# Sht3-Regulators.net
KiCad netlist of a schematic drawn in Altium Designer
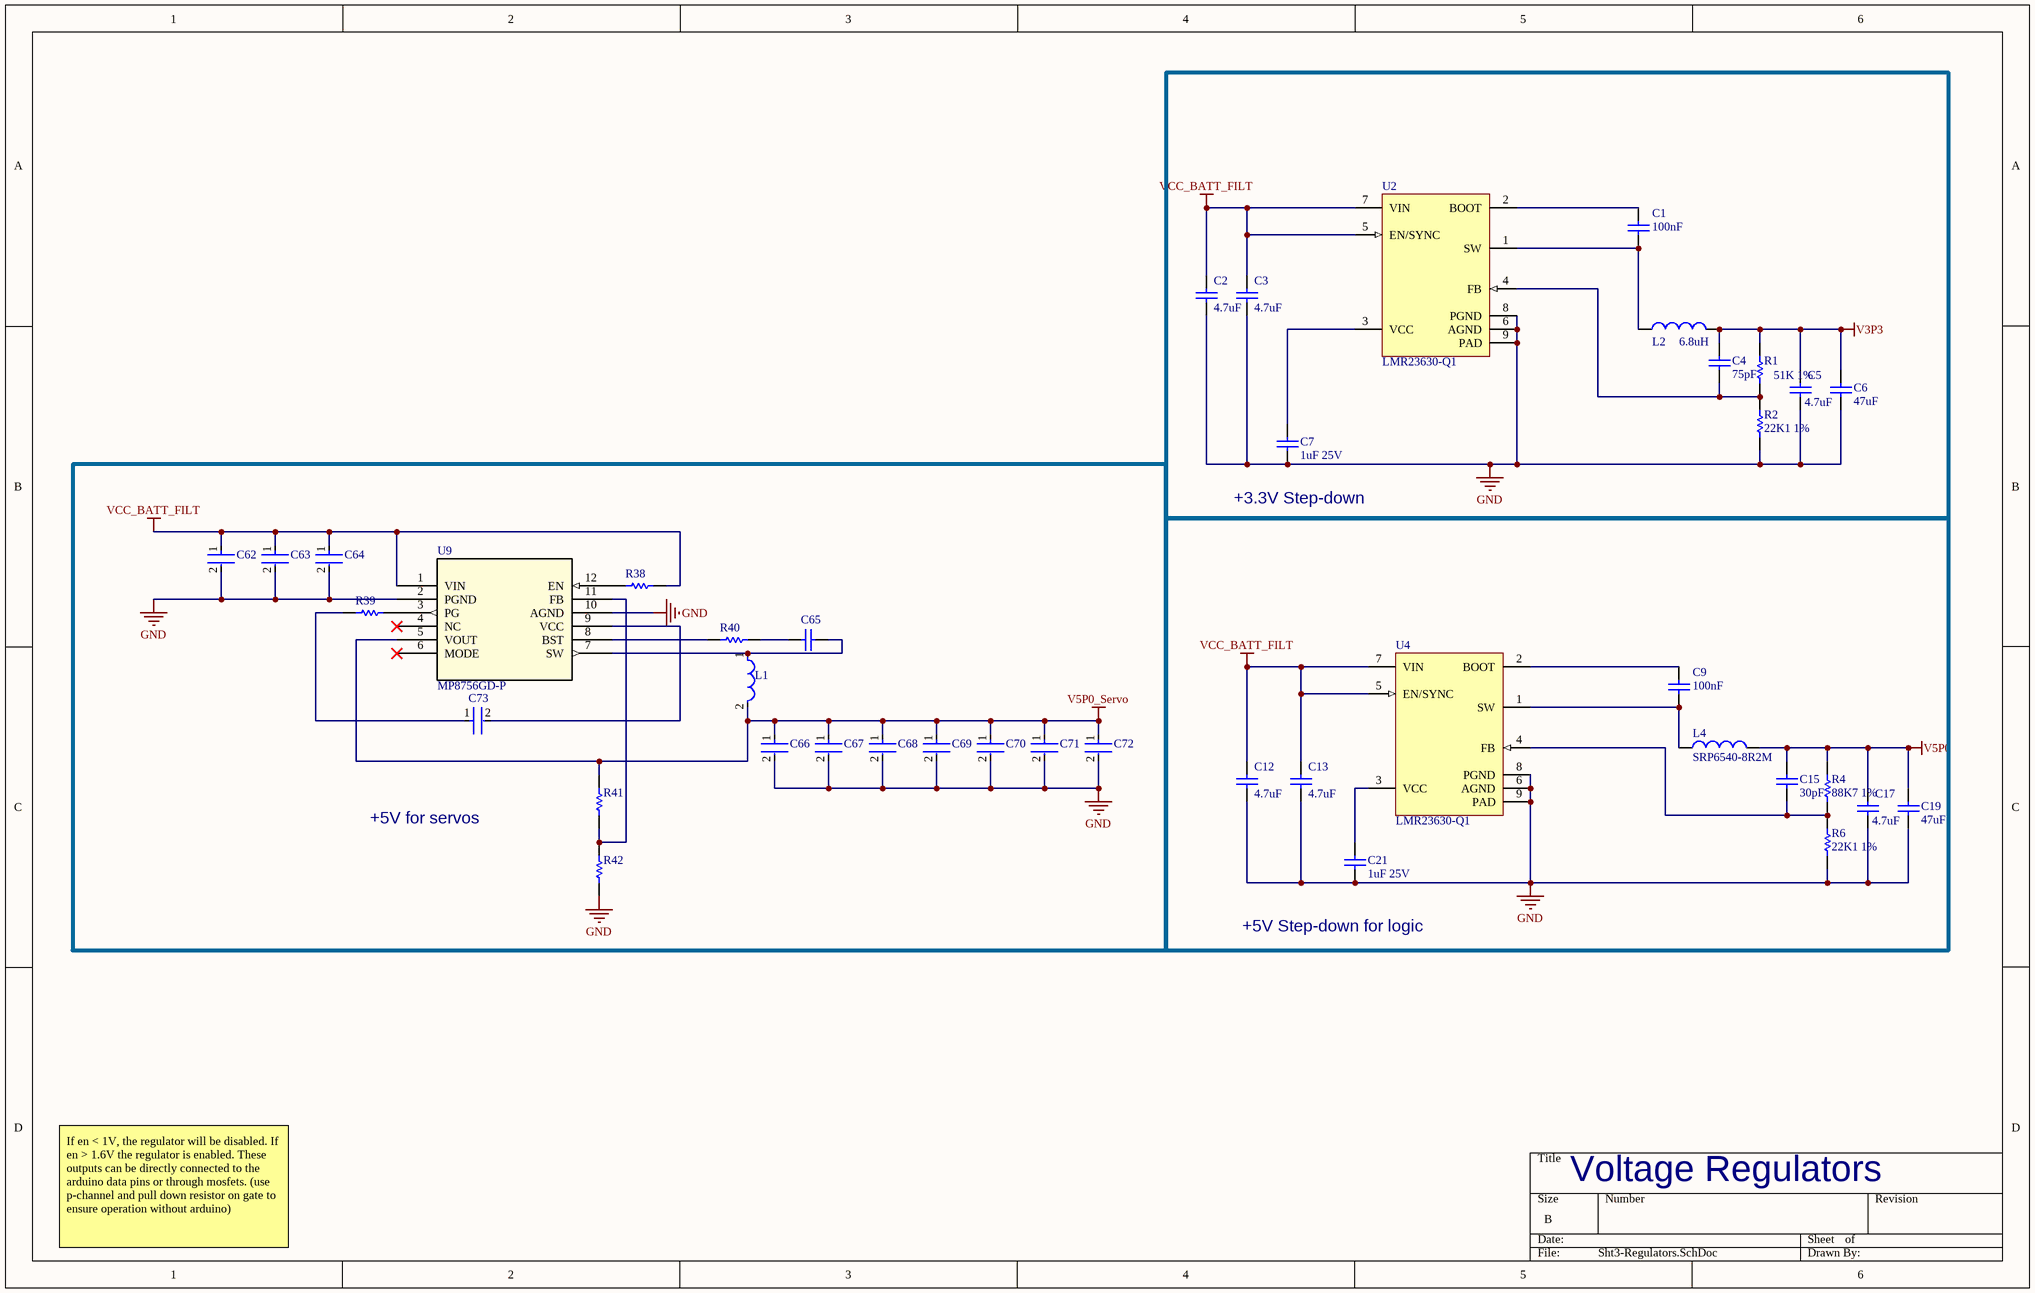
[diagram p0: Sht3-Regulators.SchDoc]

(export (version "E")
  (design (tool "Eeschema 10.0.6"))
  (components
    (comp (ref "C1")
      (value "100nF")
      (footprint "CAPC0603(1608)100_L")
      (description "CAP 100nF 100V ±10% 0603 (1608 Metric) Thickness 1mm SMD")
      (fields (field (name "TOLERANCE") "Â±10%"))
      (libsource (lib "Altium Content Vault") (part "CAP"))
    )
    (comp (ref "C2")
      (value "4.7uF")
      (footprint "CAPC1206(3216)190_L")
      (description "CAP 4.7uF 35V ±10% 1206 (3216 Metric) Thickness 1.9mm SMD")
      (fields (field (name "TOLERANCE") "Â±10%"))
      (libsource (lib "Altium Content Vault") (part "CAP"))
    )
    (comp (ref "C3")
      (value "4.7uF")
      (footprint "CAPC1206(3216)190_L")
      (description "CAP 4.7uF 35V ±10% 1206 (3216 Metric) Thickness 1.9mm SMD")
      (fields (field (name "TOLERANCE") "Â±10%"))
      (libsource (lib "Altium Content Vault") (part "CAP"))
    )
    (comp (ref "C4")
      (value "75pF")
      (footprint "CAPC0603(1608)100_L")
      (description "CAP 75pF 25V ±1% 0603 (1608 Metric) Thickness 1mm SMD")
      (fields (field (name "TOLERANCE") "Â±1%"))
      (libsource (lib "Altium Content Vault") (part "CAP"))
    )
    (comp (ref "C5")
      (value "4.7uF")
      (footprint "CAPC1206(3216)190_L")
      (description "CAP 4.7uF 35V ±10% 1206 (3216 Metric) Thickness 1.9mm SMD")
      (fields (field (name "TOLERANCE") "Â±10%"))
      (libsource (lib "Altium Content Vault") (part "CAP"))
    )
    (comp (ref "C6")
      (value "47uF")
      (footprint "CAPC1206(3216)190_L")
      (description "CAP 47uF 16V ±20% 1206 (3216 Metric) Thickness 1.9mm SMD")
      (fields (field (name "TOLERANCE") "Â±20%"))
      (libsource (lib "Altium Content Vault") (part "CAP"))
    )
    (comp (ref "C7")
      (value "1uF 25V")
      (footprint "CAPC0603(1608)100_L")
      (description "CAP 1uF 25V ±10% 0603 (1608 Metric) Thickness 1mm SMD")
      (fields (field (name "TOLERANCE") "Â±10%"))
      (libsource (lib "Altium Content Vault") (part "CAP"))
    )
    (comp (ref "C9")
      (value "100nF")
      (footprint "CAPC0603(1608)100_L")
      (description "CAP 100nF 100V ±10% 0603 (1608 Metric) Thickness 1mm SMD")
      (fields (field (name "TOLERANCE") "Â±10%"))
      (libsource (lib "Altium Content Vault") (part "CAP"))
    )
    (comp (ref "C12")
      (value "4.7uF")
      (footprint "CAPC1206(3216)190_L")
      (description "CAP 4.7uF 35V ±10% 1206 (3216 Metric) Thickness 1.9mm SMD")
      (fields (field (name "TOLERANCE") "Â±10%"))
      (libsource (lib "Altium Content Vault") (part "CAP"))
    )
    (comp (ref "C13")
      (value "4.7uF")
      (footprint "CAPC1206(3216)190_L")
      (description "CAP 4.7uF 35V ±10% 1206 (3216 Metric) Thickness 1.9mm SMD")
      (fields (field (name "TOLERANCE") "Â±10%"))
      (libsource (lib "Altium Content Vault") (part "CAP"))
    )
    (comp (ref "C15")
      (value "30pF")
      (footprint "CAPC0603(1608)100_L")
      (description "CAP 30pF 50V ±10% 0603 (1608 Metric) Thickness 1mm SMD")
      (fields (field (name "TOLERANCE") "Â±10%"))
      (libsource (lib "Altium Content Vault") (part "CAP"))
    )
    (comp (ref "C17")
      (value "4.7uF")
      (footprint "CAPC1206(3216)190_L")
      (description "CAP 4.7uF 35V ±10% 1206 (3216 Metric) Thickness 1.9mm SMD")
      (fields (field (name "TOLERANCE") "Â±10%"))
      (libsource (lib "Altium Content Vault") (part "CAP"))
    )
    (comp (ref "C19")
      (value "47uF")
      (footprint "CAPC1206(3216)190_L")
      (description "CAP 47uF 16V ±20% 1206 (3216 Metric) Thickness 1.9mm SMD")
      (fields (field (name "TOLERANCE") "Â±20%"))
      (libsource (lib "Altium Content Vault") (part "CAP"))
    )
    (comp (ref "C21")
      (value "1uF 25V")
      (footprint "CAPC0603(1608)100_L")
      (description "CAP 1uF 25V ±10% 0603 (1608 Metric) Thickness 1mm SMD")
      (fields (field (name "TOLERANCE") "Â±10%"))
      (libsource (lib "Altium Content Vault") (part "CAP"))
    )
    (comp (ref "C62")
      (value "CC0603KRX7R9BB104")
      (footprint "FP-CC0603-DA-MFG")
      (description "CAP CER 0.1UF 50V X7R 0603")
      (fields (field (name "MANUFACTURER") "YAGEO") (field (name "VOLTAGE") "50 V"))
      (libsource (lib "Altium Content Vault") (part "11868f565c42a9108669ba33697ecf6"))
    )
    (comp (ref "C63")
      (value "CL10A226MPCNUBE")
      (footprint "FP-CL10-IPC_B")
      (description "Cap Ceramic 22uF 10V X5R ±20% Pad SMD 0603 +85°C T/R")
      (fields (field (name "TOLERANCE") "20%"))
      (libsource (lib "Altium Content Vault") (part "b4654b650e69147ec39a6b967a45e02"))
    )
    (comp (ref "C64")
      (value "CL10A226MPCNUBE")
      (footprint "FP-CL10-IPC_B")
      (description "Cap Ceramic 22uF 10V X5R ±20% Pad SMD 0603 +85°C T/R")
      (fields (field (name "TOLERANCE") "20%"))
      (libsource (lib "Altium Content Vault") (part "b4654b650e69147ec39a6b967a45e02"))
    )
    (comp (ref "C65")
      (value "C0603C224K8NACTU")
      (footprint "CAPC1608X87X35NL15T15")
      (description "220nF 0603")
      (fields (field (name "MANUFACTURER") "Kemet"))
      (libsource (lib "Altium Content Vault") (part "CAP"))
    )
    (comp (ref "C66")
      (value "CL10A226MPCNUBE")
      (footprint "FP-CL10-IPC_B")
      (description "Cap Ceramic 22uF 10V X5R ±20% Pad SMD 0603 +85°C T/R")
      (fields (field (name "TOLERANCE") "20%"))
      (libsource (lib "Altium Content Vault") (part "b4654b650e69147ec39a6b967a45e02"))
    )
    (comp (ref "C67")
      (value "CL10A226MPCNUBE")
      (footprint "FP-CL10-IPC_B")
      (description "Cap Ceramic 22uF 10V X5R ±20% Pad SMD 0603 +85°C T/R")
      (fields (field (name "TOLERANCE") "20%"))
      (libsource (lib "Altium Content Vault") (part "b4654b650e69147ec39a6b967a45e02"))
    )
    (comp (ref "C68")
      (value "CL10A226MPCNUBE")
      (footprint "FP-CL10-IPC_B")
      (description "Cap Ceramic 22uF 10V X5R ±20% Pad SMD 0603 +85°C T/R")
      (fields (field (name "TOLERANCE") "20%"))
      (libsource (lib "Altium Content Vault") (part "b4654b650e69147ec39a6b967a45e02"))
    )
    (comp (ref "C69")
      (value "CL10A226MPCNUBE")
      (footprint "FP-CL10-IPC_B")
      (description "Cap Ceramic 22uF 10V X5R ±20% Pad SMD 0603 +85°C T/R")
      (fields (field (name "TOLERANCE") "20%"))
      (libsource (lib "Altium Content Vault") (part "b4654b650e69147ec39a6b967a45e02"))
    )
    (comp (ref "C70")
      (value "CC0603KRX7R9BB104")
      (footprint "FP-CC0603-DA-MFG")
      (description "CAP CER 0.1UF 50V X7R 0603")
      (fields (field (name "MANUFACTURER") "YAGEO") (field (name "VOLTAGE") "50 V"))
      (libsource (lib "Altium Content Vault") (part "11868f565c42a9108669ba33697ecf6"))
    )
    (comp (ref "C71")
      (value "CC0603KRX7R9BB104")
      (footprint "FP-CC0603-DA-MFG")
      (description "CAP CER 0.1UF 50V X7R 0603")
      (fields (field (name "MANUFACTURER") "YAGEO") (field (name "VOLTAGE") "50 V"))
      (libsource (lib "Altium Content Vault") (part "11868f565c42a9108669ba33697ecf6"))
    )
    (comp (ref "C72")
      (value "CC0603KRX7R9BB104")
      (footprint "FP-CC0603-DA-MFG")
      (description "CAP CER 0.1UF 50V X7R 0603")
      (fields (field (name "MANUFACTURER") "YAGEO") (field (name "VOLTAGE") "50 V"))
      (libsource (lib "Altium Content Vault") (part "11868f565c42a9108669ba33697ecf6"))
    )
    (comp (ref "C73")
      (value "CC0603KRX7R7BB105")
      (footprint "FP-CC0603-DA-MFG")
      (description "CAP CER 1UF 16V X7R 0603")
      (fields (field (name "TOLERANCE") "0.1") (field (name "MANUFACTURER") "YAGEO"))
      (libsource (lib "Altium Content Vault") (part "11868f565c42a9108669ba33697ecf6"))
    )
    (comp (ref "L1")
      (value "IHLP2525CZER1R5M01")
      (footprint "FP-IHLP-2525CZ-FP_2_413x3-MFG")
      (description "Commercial Inductors, High Saturation Series 1.5uH 9A 15mΩ 20%")
      (fields (field (name "TOLERANCE") "20%"))
      (libsource (lib "Altium Content Vault") (part "725321dda6339637d4d059423bc1c3c"))
    )
    (comp (ref "L2")
      (value "6.8uH")
      (footprint "BOURNS SRP5030T")
      (fields
        (field (name "MANUFACTURER") "Bourns Inc.")
        (field (name "MANUFACTURER PART NUMBER") "SRP5030TA-6R8M")
        (field (name "TOLERANCE") "±20%")
      )
      (libsource (lib "CMR_Miscellaneous_Devices") (part "SRP5030TA"))
    )
    (comp (ref "L4")
      (value "SRP6540-8R2M")
      (footprint "BOURNS SRP5030T")
      (libsource (lib "TAUV-Lib") (part "SRP5030TA_8R2"))
    )
    (comp (ref "R1")
      (value "51K 1%")
      (footprint "RESC0603(1608)_L")
      (description "51K 0.1W 1% 0603 (1608 Metric)  SMD")
      (fields (field (name "TOLERANCE") "1 %") (field (name "POWER") "0.1 W"))
      (libsource (lib "Altium Content Vault") (part "RES"))
    )
    (comp (ref "R2")
      (value "22K1 1%")
      (footprint "RESC0603(1608)_L")
      (description "22K1 0.1W 1% 0603 (1608 Metric)  SMD")
      (fields (field (name "TOLERANCE") "1 %") (field (name "POWER") "0.1 W"))
      (libsource (lib "Altium Content Vault") (part "RES"))
    )
    (comp (ref "R4")
      (value "88K7 1%")
      (footprint "RESC0603(1608)_L")
      (description "88K7 0.1W 1% 0603 (1608 Metric)  SMD")
      (fields (field (name "TOLERANCE") "1 %") (field (name "POWER") "0.1 W"))
      (libsource (lib "Altium Content Vault") (part "RES"))
    )
    (comp (ref "R6")
      (value "22K1 1%")
      (footprint "RESC0603(1608)_L")
      (description "22K1 0.1W 1% 0603 (1608 Metric)  SMD")
      (fields (field (name "TOLERANCE") "1 %") (field (name "POWER") "0.1 W"))
      (libsource (lib "Altium Content Vault") (part "RES"))
    )
    (comp (ref "R38")
      (value "CRCW06031M50FKEA")
      (footprint "RESC1609X50X30NL10T20")
      (description "1M5 0603")
      (fields (field (name "MANUFACTURER") "Vishay Dale"))
      (libsource (lib "Altium Content Vault") (part "RES"))
    )
    (comp (ref "R39")
      (value "ERJ-3EKF1003V")
      (footprint "RESC1608X55X30ML15T15")
      (description "100k 0603")
      (fields (field (name "MANUFACTURER") "Panasonic"))
      (libsource (lib "Altium Content Vault") (part "RES"))
    )
    (comp (ref "R40")
      (value "ERJ-3RQF3R3V")
      (footprint "RESC1608X55X30NL15T15")
      (description "3R3 0603")
      (fields (field (name "MANUFACTURER") "Panasonic"))
      (libsource (lib "Altium Content Vault") (part "RES"))
    )
    (comp (ref "R41")
      (value "ERA3AEB4122V")
      (footprint "RESC1608X55X30LL20T20")
      (description "41k2 0603")
      (fields (field (name "MANUFACTURER") "Panasonic"))
      (libsource (lib "Altium Content Vault") (part "RES"))
    )
    (comp (ref "R42")
      (value "ERJ-3EKF5601V")
      (footprint "RESC1609X55X30LL15T15")
      (description "Chip Resistor, 5.6 KOhm, +/- 1%, 0.1 W, -55 to 155 degC, 0603 (1608 Metric), RoHS, Tape and Reel")
      (libsource (lib "Altium Content Vault") (part "RES-2"))
    )
    (comp (ref "U2")
      (value "LMR23630-Q1")
      (footprint "DDA0008E_N")
      (fields
        (field (name "MANUFACTURER") "Texas Instruments")
        (field (name "MANUFACTURER PART NUMBER") "LMR23630AFQDDARQ1")
      )
      (libsource (lib "CMR_Miscellaneous_Devices") (part "LMR23630-Q1"))
    )
    (comp (ref "U4")
      (value "LMR23630-Q1")
      (footprint "DDA0008E_N")
      (fields
        (field (name "MANUFACTURER") "Texas Instruments")
        (field (name "MANUFACTURER PART NUMBER") "LMR23630AFQDDARQ1")
      )
      (libsource (lib "CMR_Miscellaneous_Devices") (part "LMR23630-Q1"))
    )
    (comp (ref "U9")
      (value "MP8756GD-P")
      (footprint "QFN-12_MP8756_MNP")
      (description "No Description Available")
      (libsource (lib "TAUV-Lib") (part "MP8756GD-P"))
    )
  )
  (nets
    (net (code "1") (name "GND") (class "Default")
      (node (ref "C12") (pin "1") (pinfunction "1_1") (pintype "passive"))
      (node (ref "C13") (pin "1") (pinfunction "1_1") (pintype "passive"))
      (node (ref "C17") (pin "1") (pinfunction "1_1") (pintype "passive"))
      (node (ref "C19") (pin "1") (pinfunction "1_1") (pintype "passive"))
      (node (ref "C2") (pin "1") (pinfunction "1_1") (pintype "passive"))
      (node (ref "C21") (pin "1") (pinfunction "1_1") (pintype "passive"))
      (node (ref "C3") (pin "1") (pinfunction "1_1") (pintype "passive"))
      (node (ref "C5") (pin "1") (pinfunction "1_1") (pintype "passive"))
      (node (ref "C6") (pin "1") (pinfunction "1_1") (pintype "passive"))
      (node (ref "C62") (pin "2") (pinfunction "2_2") (pintype "passive"))
      (node (ref "C63") (pin "2") (pinfunction "2_2") (pintype "passive"))
      (node (ref "C64") (pin "2") (pinfunction "2_2") (pintype "passive"))
      (node (ref "C66") (pin "2") (pinfunction "2_2") (pintype "passive"))
      (node (ref "C67") (pin "2") (pinfunction "2_2") (pintype "passive"))
      (node (ref "C68") (pin "2") (pinfunction "2_2") (pintype "passive"))
      (node (ref "C69") (pin "2") (pinfunction "2_2") (pintype "passive"))
      (node (ref "C7") (pin "1") (pinfunction "1_1") (pintype "passive"))
      (node (ref "C70") (pin "2") (pinfunction "2_2") (pintype "passive"))
      (node (ref "C71") (pin "2") (pinfunction "2_2") (pintype "passive"))
      (node (ref "C72") (pin "2") (pinfunction "2_2") (pintype "passive"))
      (node (ref "R2") (pin "1") (pinfunction "1_1") (pintype "passive"))
      (node (ref "R42") (pin "2") (pinfunction "2_2") (pintype "passive"))
      (node (ref "R6") (pin "1") (pinfunction "1_1") (pintype "passive"))
      (node (ref "U2") (pin "6") (pinfunction "AGND_6") (pintype "passive"))
      (node (ref "U2") (pin "8") (pinfunction "PGND_8") (pintype "passive"))
      (node (ref "U2") (pin "9") (pinfunction "PAD_9") (pintype "passive"))
      (node (ref "U4") (pin "6") (pinfunction "AGND_6") (pintype "passive"))
      (node (ref "U4") (pin "8") (pinfunction "PGND_8") (pintype "passive"))
      (node (ref "U4") (pin "9") (pinfunction "PAD_9") (pintype "passive"))
      (node (ref "U9") (pin "10") (pinfunction "AGND_10") (pintype "power_in"))
      (node (ref "U9") (pin "2") (pinfunction "PGND_2") (pintype "power_in"))
    )
    (net (code "2") (name "Net-(C65-Pad1)") (class "Default")
      (node (ref "C65") (pin "1") (pinfunction "1_1") (pintype "passive"))
      (node (ref "R40") (pin "2") (pinfunction "2_2") (pintype "passive"))
    )
    (net (code "3") (name "Net-(C73-Pad1)") (class "Default")
      (node (ref "C73") (pin "1") (pinfunction "1_1") (pintype "passive"))
      (node (ref "R39") (pin "1") (pinfunction "1_1") (pintype "passive"))
    )
    (net (code "4") (name "Net-(U2-BOOT)") (class "Default")
      (node (ref "C1") (pin "2") (pinfunction "2_2") (pintype "passive"))
      (node (ref "U2") (pin "2") (pinfunction "BOOT_2") (pintype "passive"))
    )
    (net (code "5") (name "Net-(U2-FB)") (class "Default")
      (node (ref "C4") (pin "1") (pinfunction "1_1") (pintype "passive"))
      (node (ref "R1") (pin "1") (pinfunction "1_1") (pintype "passive"))
      (node (ref "R2") (pin "2") (pinfunction "2_2") (pintype "passive"))
      (node (ref "U2") (pin "4") (pinfunction "FB_4") (pintype "input"))
    )
    (net (code "6") (name "Net-(U2-SW)") (class "Default")
      (node (ref "C1") (pin "1") (pinfunction "1_1") (pintype "passive"))
      (node (ref "L2") (pin "1") (pinfunction "1_1") (pintype "passive"))
      (node (ref "U2") (pin "1") (pinfunction "SW_1") (pintype "passive"))
    )
    (net (code "7") (name "Net-(U2-VCC)") (class "Default")
      (node (ref "C7") (pin "2") (pinfunction "2_2") (pintype "passive"))
      (node (ref "U2") (pin "3") (pinfunction "VCC_3") (pintype "passive"))
    )
    (net (code "8") (name "Net-(U4-BOOT)") (class "Default")
      (node (ref "C9") (pin "2") (pinfunction "2_2") (pintype "passive"))
      (node (ref "U4") (pin "2") (pinfunction "BOOT_2") (pintype "passive"))
    )
    (net (code "9") (name "Net-(U4-FB)") (class "Default")
      (node (ref "C15") (pin "1") (pinfunction "1_1") (pintype "passive"))
      (node (ref "R4") (pin "1") (pinfunction "1_1") (pintype "passive"))
      (node (ref "R6") (pin "2") (pinfunction "2_2") (pintype "passive"))
      (node (ref "U4") (pin "4") (pinfunction "FB_4") (pintype "input"))
    )
    (net (code "10") (name "Net-(U4-SW)") (class "Default")
      (node (ref "C9") (pin "1") (pinfunction "1_1") (pintype "passive"))
      (node (ref "L4") (pin "1") (pinfunction "1_1") (pintype "passive"))
      (node (ref "U4") (pin "1") (pinfunction "SW_1") (pintype "passive"))
    )
    (net (code "11") (name "Net-(U4-VCC)") (class "Default")
      (node (ref "C21") (pin "2") (pinfunction "2_2") (pintype "passive"))
      (node (ref "U4") (pin "3") (pinfunction "VCC_3") (pintype "passive"))
    )
    (net (code "12") (name "Net-(U9-BST)") (class "Default")
      (node (ref "R40") (pin "1") (pinfunction "1_1") (pintype "passive"))
      (node (ref "U9") (pin "8") (pinfunction "BST_8") (pintype "power_in"))
    )
    (net (code "13") (name "Net-(U9-EN)") (class "Default")
      (node (ref "R38") (pin "1") (pinfunction "1_1") (pintype "passive"))
      (node (ref "U9") (pin "12") (pinfunction "EN_12") (pintype "input"))
    )
    (net (code "14") (name "Net-(U9-FB)") (class "Default")
      (node (ref "R41") (pin "1") (pinfunction "1_1") (pintype "passive"))
      (node (ref "R42") (pin "1") (pinfunction "1_1") (pintype "passive"))
      (node (ref "U9") (pin "11") (pinfunction "FB_11") (pintype "passive"))
    )
    (net (code "15") (name "Net-(U9-PG)") (class "Default")
      (node (ref "R39") (pin "2") (pinfunction "2_2") (pintype "passive"))
      (node (ref "U9") (pin "3") (pinfunction "PG_3") (pintype "output"))
    )
    (net (code "16") (name "Net-(U9-SW)") (class "Default")
      (node (ref "C65") (pin "2") (pinfunction "2_2") (pintype "passive"))
      (node (ref "L1") (pin "1") (pinfunction "1_1") (pintype "passive"))
      (node (ref "U9") (pin "7") (pinfunction "SW_7") (pintype "output"))
    )
    (net (code "17") (name "Net-(U9-VCC)") (class "Default")
      (node (ref "C73") (pin "2") (pinfunction "2_2") (pintype "passive"))
      (node (ref "U9") (pin "9") (pinfunction "VCC_9") (pintype "power_in"))
    )
    (net (code "18") (name "V3P3") (class "Default")
      (node (ref "C4") (pin "2") (pinfunction "2_2") (pintype "passive"))
      (node (ref "C5") (pin "2") (pinfunction "2_2") (pintype "passive"))
      (node (ref "C6") (pin "2") (pinfunction "2_2") (pintype "passive"))
      (node (ref "L2") (pin "2") (pinfunction "2_2") (pintype "passive"))
      (node (ref "R1") (pin "2") (pinfunction "2_2") (pintype "passive"))
    )
    (net (code "19") (name "V5P0") (class "Default")
      (node (ref "C15") (pin "2") (pinfunction "2_2") (pintype "passive"))
      (node (ref "C17") (pin "2") (pinfunction "2_2") (pintype "passive"))
      (node (ref "C19") (pin "2") (pinfunction "2_2") (pintype "passive"))
      (node (ref "L4") (pin "2") (pinfunction "2_2") (pintype "passive"))
      (node (ref "R4") (pin "2") (pinfunction "2_2") (pintype "passive"))
    )
    (net (code "20") (name "V5P0_Servo") (class "Default")
      (node (ref "C66") (pin "1") (pinfunction "1_1") (pintype "passive"))
      (node (ref "C67") (pin "1") (pinfunction "1_1") (pintype "passive"))
      (node (ref "C68") (pin "1") (pinfunction "1_1") (pintype "passive"))
      (node (ref "C69") (pin "1") (pinfunction "1_1") (pintype "passive"))
      (node (ref "C70") (pin "1") (pinfunction "1_1") (pintype "passive"))
      (node (ref "C71") (pin "1") (pinfunction "1_1") (pintype "passive"))
      (node (ref "C72") (pin "1") (pinfunction "1_1") (pintype "passive"))
      (node (ref "L1") (pin "2") (pinfunction "2_2") (pintype "passive"))
      (node (ref "R41") (pin "2") (pinfunction "2_2") (pintype "passive"))
      (node (ref "U9") (pin "5") (pinfunction "VOUT_5") (pintype "power_in"))
    )
    (net (code "21") (name "VCC_BATT_FILT") (class "Default")
      (node (ref "C12") (pin "2") (pinfunction "2_2") (pintype "passive"))
      (node (ref "C13") (pin "2") (pinfunction "2_2") (pintype "passive"))
      (node (ref "C2") (pin "2") (pinfunction "2_2") (pintype "passive"))
      (node (ref "C3") (pin "2") (pinfunction "2_2") (pintype "passive"))
      (node (ref "C62") (pin "1") (pinfunction "1_1") (pintype "passive"))
      (node (ref "C63") (pin "1") (pinfunction "1_1") (pintype "passive"))
      (node (ref "C64") (pin "1") (pinfunction "1_1") (pintype "passive"))
      (node (ref "R38") (pin "2") (pinfunction "2_2") (pintype "passive"))
      (node (ref "U2") (pin "5") (pinfunction "EN/SYNC_5") (pintype "input"))
      (node (ref "U2") (pin "7") (pinfunction "VIN_7") (pintype "passive"))
      (node (ref "U4") (pin "5") (pinfunction "EN/SYNC_5") (pintype "input"))
      (node (ref "U4") (pin "7") (pinfunction "VIN_7") (pintype "passive"))
      (node (ref "U9") (pin "1") (pinfunction "VIN_1") (pintype "power_in"))
    )
    (net (code "22") (name "unconnected-(U9-MODE-Pad6)") (class "Default")
      (node (ref "U9") (pin "6") (pinfunction "MODE_6") (pintype "passive+no_connect"))
    )
    (net (code "23") (name "unconnected-(U9-NC-Pad4)") (class "Default")
      (node (ref "U9") (pin "4") (pinfunction "NC_4") (pintype "passive+no_connect"))
    )
  )
)
